# AC_DC.net
KiCad netlist of a schematic drawn in Altium Designer
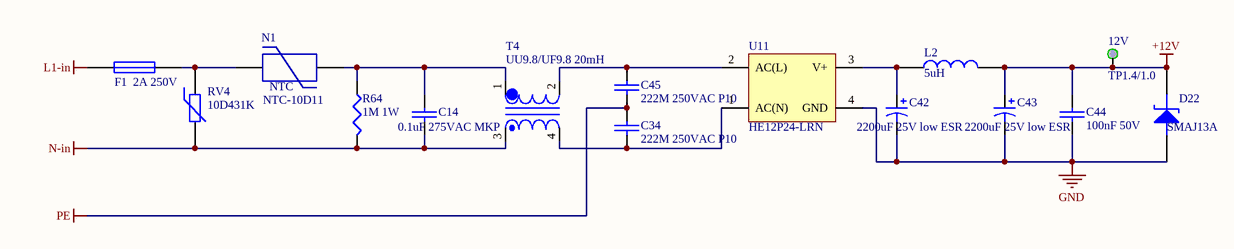
[diagram p0: AC_DC.SchDoc]

(export (version "E")
  (design (tool "Eeschema 10.0.6"))
  (components
    (comp (ref "12V")
      (value "TP1.4/1.0")
      (footprint "UserPcbLib:TP1.4/1.0")
      (libsource (lib "UserSchlib") (part "TP1.4/1.0"))
    )
    (comp (ref "C14")
      (value "0.1uF 275VAC MKP")
      (footprint "UserPcbLib:0.1uF 275VAC MKP")
      (description "Capacitor")
      (libsource (lib "*") (part "CAP"))
    )
    (comp (ref "C34")
      (value "222M 250VAC P10")
      (footprint "Capacitor Non-Polar Disc:CAPRD10-9x5")
      (description "Capacitor")
      (libsource (lib "*") (part "CAP"))
    )
    (comp (ref "C42")
      (value "2200uF 25V low ESR")
      (footprint "Capacitor Polar Radial Cylinder:CAPPR7.5-16x25")
      (description "Polarized Capacitor (Radial)")
      (fields (field (name "PUBLISHER") "Altium Limited"))
      (libsource (lib "Miscellaneous Devices") (part "Cap Pol1"))
    )
    (comp (ref "C43")
      (value "2200uF 25V low ESR")
      (footprint "Capacitor Polar Radial Cylinder:CAPPR7.5-16x25")
      (description "Polarized Capacitor (Radial)")
      (fields (field (name "PUBLISHER") "Altium Limited"))
      (libsource (lib "Miscellaneous Devices") (part "Cap Pol1"))
    )
    (comp (ref "C44")
      (value "100nF 50V")
      (footprint "IPC-7352 Chip_Capacitor_N:CAPC2012N")
      (description "Capacitor")
      (libsource (lib "*") (part "CAP"))
    )
    (comp (ref "C45")
      (value "222M 250VAC P10")
      (footprint "Capacitor Non-Polar Disc:CAPRD10-9x5")
      (description "Capacitor")
      (libsource (lib "*") (part "CAP"))
    )
    (comp (ref "D22")
      (value "SMAJ13A")
      (footprint "Small Outline Diode - 2 C-Bend Leads:DSO-C2/G1.6")
      (description "Zener Diode")
      (fields (field (name "MANUFACTURER") "Littlefuse"))
      (libsource (lib "*") (part "ZENER2"))
    )
    (comp (ref "F1")
      (value "2A 250V")
      (footprint "UserPcbLib:FUSE-CASE-23mm")
      (description "Fuse socket w/ cover")
      (libsource (lib "*") (part "FUSE1"))
    )
    (comp (ref "L2")
      (value "5uH")
      (footprint "UserPcbLib:Inductor9.5-11x21")
      (description "Radial type Inductor 2A")
      (libsource (lib "*") (part "INDUCTOR"))
    )
    (comp (ref "N1")
      (value "NTC-10D11")
      (footprint "UserPcbLib:10D431K")
      (description "Thermister")
      (libsource (lib "UserSchlib") (part "NTC"))
    )
    (comp (ref "R64")
      (value "1M 1W")
      (footprint "Resistor - Axial:RES15-13.5X5")
      (description "Resistor")
      (libsource (lib "Miscellaneous Devices") (part "Res3"))
    )
    (comp (ref "RV4")
      (value "10D431K")
      (footprint "UserPcbLib:10D431K")
      (description "Varistor (Voltage-Sensitive Resistor)")
      (fields (field (name "PUBLISHER") "Altium Limited"))
      (libsource (lib "Miscellaneous Devices") (part "Res Varistor"))
    )
    (comp (ref "T4")
      (value "UU9.8/UF9.8 20mH")
      (footprint "UserPcbLib:UU9.8/UF9.8")
      (description "Balum")
      (libsource (lib "UserSchlib") (part "Balum UU9.8/UF9.8"))
    )
    (comp (ref "U11")
      (value "HE12P24-LRN")
      (footprint "UserPcbLib:HIECUBE_AC_DC_24W")
      (description "HICUBE AC/DC 24W 12V")
      (libsource (lib "UserSchlib") (part "HIECUBE_AC-DC_24W"))
    )
  )
  (nets
    (net (code "1") (name "+12V") (class "Default")
      (node (ref "12V") (pin "1") (pinfunction "1_1") (pintype "passive"))
      (node (ref "C43") (pin "1") (pinfunction "1_1") (pintype "passive"))
      (node (ref "C44") (pin "2") (pinfunction "2_2") (pintype "passive"))
      (node (ref "D22") (pin "2") (pinfunction "K_2") (pintype "passive"))
      (node (ref "L2") (pin "2") (pinfunction "2_2") (pintype "passive"))
    )
    (net (code "2") (name "GND") (class "Default")
      (node (ref "C42") (pin "2") (pinfunction "2_2") (pintype "passive"))
      (node (ref "C43") (pin "2") (pinfunction "2_2") (pintype "passive"))
      (node (ref "C44") (pin "1") (pinfunction "1_1") (pintype "passive"))
      (node (ref "D22") (pin "1") (pinfunction "A_1") (pintype "passive"))
      (node (ref "U11") (pin "4") (pinfunction "GND_4") (pintype "passive"))
    )
    (net (code "3") (name "L1-in") (class "Default")
      (node (ref "F1") (pin "1") (pinfunction "1_1") (pintype "passive"))
    )
    (net (code "4") (name "N-in") (class "Default")
      (node (ref "C14") (pin "1") (pinfunction "1_1") (pintype "passive"))
      (node (ref "R64") (pin "2") (pinfunction "2_2") (pintype "passive"))
      (node (ref "RV4") (pin "2") (pinfunction "2_2") (pintype "passive"))
      (node (ref "T4") (pin "3") (pintype "passive"))
    )
    (net (code "5") (name "Net-(C14-Pad2)") (class "Default")
      (node (ref "C14") (pin "2") (pinfunction "2_2") (pintype "passive"))
      (node (ref "N1") (pin "2") (pinfunction "2_2") (pintype "passive"))
      (node (ref "R64") (pin "1") (pinfunction "1_1") (pintype "passive"))
      (node (ref "T4") (pin "1") (pintype "passive"))
    )
    (net (code "6") (name "Net-(F1-Pad2)") (class "Default")
      (node (ref "F1") (pin "2") (pinfunction "2_2") (pintype "passive"))
      (node (ref "N1") (pin "1") (pinfunction "1_1") (pintype "passive"))
      (node (ref "RV4") (pin "1") (pinfunction "1_1") (pintype "passive"))
    )
    (net (code "7") (name "Net-(U11-AC(L))") (class "Default")
      (node (ref "C45") (pin "2") (pinfunction "2_2") (pintype "passive"))
      (node (ref "T4") (pin "2") (pintype "passive"))
      (node (ref "U11") (pin "2") (pinfunction "AC(L)_2") (pintype "passive"))
    )
    (net (code "8") (name "Net-(U11-AC(N))") (class "Default")
      (node (ref "C34") (pin "1") (pinfunction "1_1") (pintype "passive"))
      (node (ref "T4") (pin "4") (pintype "passive"))
      (node (ref "U11") (pin "1") (pinfunction "AC(N)_1") (pintype "passive"))
    )
    (net (code "9") (name "Net-(U11-V+)") (class "Default")
      (node (ref "C42") (pin "1") (pinfunction "1_1") (pintype "passive"))
      (node (ref "L2") (pin "1") (pinfunction "1_1") (pintype "passive"))
      (node (ref "U11") (pin "3") (pinfunction "V+_3") (pintype "passive"))
    )
    (net (code "10") (name "PE") (class "Default")
      (node (ref "C34") (pin "2") (pinfunction "2_2") (pintype "passive"))
      (node (ref "C45") (pin "1") (pinfunction "1_1") (pintype "passive"))
    )
  )
)
